# sismikenkazmod.net
KiCad netlist of a schematic drawn in Altium Designer
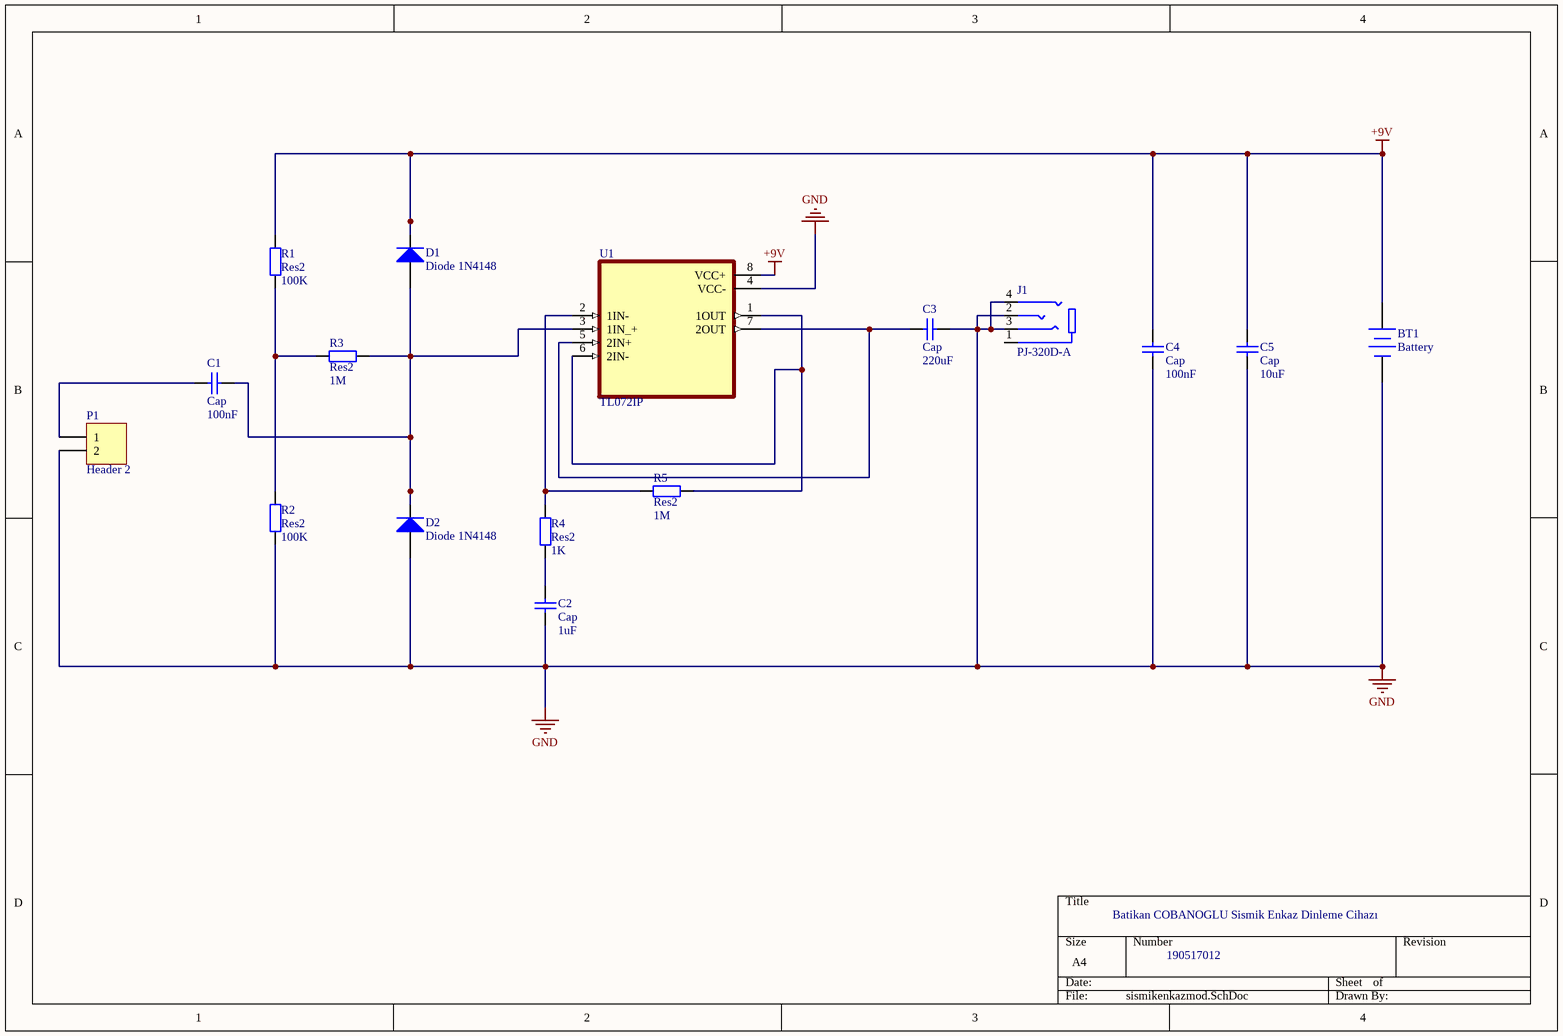
[diagram p0: sismikenkazmod.SchDoc]

(export (version "E")
  (design (tool "Eeschema 10.0.6"))
  (components
    (comp (ref "BT1")
      (value "Battery")
      (footprint "BAT-2")
      (description "Multicell Battery")
      (fields (field (name "PUBLISHER") "Altium Limited"))
      (libsource (lib "Miscellaneous Devices") (part "Battery"))
    )
    (comp (ref "C1")
      (value "Cap")
      (footprint "RAD-0.3")
      (description "Capacitor")
      (fields (field (name "ALTIUM_VALUE") "100nF") (field (name "PUBLISHER") "Altium Limited"))
      (libsource (lib "Miscellaneous Devices") (part "Cap"))
    )
    (comp (ref "C2")
      (value "Cap")
      (footprint "RAD-0.3")
      (description "Capacitor")
      (fields (field (name "ALTIUM_VALUE") "1uF") (field (name "PUBLISHER") "Altium Limited"))
      (libsource (lib "Miscellaneous Devices") (part "Cap"))
    )
    (comp (ref "C3")
      (value "Cap")
      (footprint "RAD-0.3")
      (description "Capacitor")
      (fields (field (name "ALTIUM_VALUE") "220uF") (field (name "PUBLISHER") "Altium Limited"))
      (libsource (lib "Miscellaneous Devices") (part "Cap"))
    )
    (comp (ref "C4")
      (value "Cap")
      (footprint "RAD-0.3")
      (description "Capacitor")
      (fields (field (name "ALTIUM_VALUE") "100nF") (field (name "PUBLISHER") "Altium Limited"))
      (libsource (lib "Miscellaneous Devices") (part "Cap"))
    )
    (comp (ref "C5")
      (value "Cap")
      (footprint "RAD-0.3")
      (description "Capacitor")
      (fields (field (name "ALTIUM_VALUE") "10uF") (field (name "PUBLISHER") "Altium Limited"))
      (libsource (lib "Miscellaneous Devices") (part "Cap"))
    )
    (comp (ref "D1")
      (value "Diode 1N4148")
      (footprint "DO-35")
      (description "High Conductance Fast Diode")
      (fields (field (name "PUBLISHER") "Altium Limited"))
      (libsource (lib "Miscellaneous Devices") (part "Diode 1N4148"))
    )
    (comp (ref "D2")
      (value "Diode 1N4148")
      (footprint "DO-35")
      (description "High Conductance Fast Diode")
      (fields (field (name "PUBLISHER") "Altium Limited"))
      (libsource (lib "Miscellaneous Devices") (part "Diode 1N4148"))
    )
    (comp (ref "J1")
      (value "PJ-320D-A")
      (footprint "HRO_PJ-320D-A")
      (description "Headphone jack 0.5A 30V DC 100 mÎ©")
      (fields (field (name "MF") "HRO Electronics Co., Ltd."))
      (libsource (lib "PJ-320D-A") (part "PJ-320D-A"))
    )
    (comp (ref "P1")
      (value "Header 2")
      (footprint "HDR1X2")
      (description "Header, 2-Pin")
      (fields (field (name "PUBLISHER") "Altium Limited"))
      (libsource (lib "Miscellaneous Connectors") (part "Header 2"))
    )
    (comp (ref "R1")
      (value "Res2")
      (footprint "AXIAL-0.4")
      (description "Resistor")
      (fields (field (name "ALTIUM_VALUE") "100K") (field (name "PUBLISHER") "Altium Limited"))
      (libsource (lib "") (part "Res2_1"))
    )
    (comp (ref "R2")
      (value "Res2")
      (footprint "AXIAL-0.4")
      (description "Resistor")
      (fields (field (name "ALTIUM_VALUE") "100K") (field (name "PUBLISHER") "Altium Limited"))
      (libsource (lib "") (part "Res2_1"))
    )
    (comp (ref "R3")
      (value "Res2")
      (footprint "AXIAL-0.4")
      (description "Resistor")
      (fields (field (name "ALTIUM_VALUE") "1M") (field (name "PUBLISHER") "Altium Limited"))
      (libsource (lib "Miscellaneous Devices") (part "Res2"))
    )
    (comp (ref "R4")
      (value "Res2")
      (footprint "AXIAL-0.4")
      (description "Resistor")
      (fields (field (name "ALTIUM_VALUE") "1K") (field (name "PUBLISHER") "Altium Limited"))
      (libsource (lib "") (part "Res2_1"))
    )
    (comp (ref "R5")
      (value "Res2")
      (footprint "AXIAL-0.4")
      (description "Resistor")
      (fields (field (name "ALTIUM_VALUE") "1M") (field (name "PUBLISHER") "Altium Limited"))
      (libsource (lib "Miscellaneous Devices") (part "Res2"))
    )
    (comp (ref "U1")
      (value "TL072IP")
      (footprint "DIP794W45P254L959H508Q8")
      (description "Dual, 30-V, 3-MHz, high slew rate (13-V/Âµs), In to V+, JFET-input op amp")
      (fields (field (name "MF") "Texas Instruments"))
      (libsource (lib "TL072IP") (part "TL072IP"))
    )
  )
  (nets
    (net (code "1") (name "+9V") (class "Default")
      (node (ref "BT1") (pin "1") (pinfunction "+_1") (pintype "passive"))
      (node (ref "C4") (pin "1") (pinfunction "1_1") (pintype "passive"))
      (node (ref "C5") (pin "1") (pinfunction "1_1") (pintype "passive"))
      (node (ref "D1") (pin "2") (pinfunction "K_2") (pintype "passive"))
      (node (ref "R1") (pin "1") (pinfunction "1_1") (pintype "passive"))
      (node (ref "U1") (pin "8") (pinfunction "VCC+_8") (pintype "power_in"))
    )
    (net (code "2") (name "GND") (class "Default")
      (node (ref "BT1") (pin "2") (pinfunction "-_2") (pintype "passive"))
      (node (ref "C2") (pin "1") (pinfunction "1_1") (pintype "passive"))
      (node (ref "C3") (pin "2") (pinfunction "2_2") (pintype "passive"))
      (node (ref "C4") (pin "2") (pinfunction "2_2") (pintype "passive"))
      (node (ref "C5") (pin "2") (pinfunction "2_2") (pintype "passive"))
      (node (ref "D2") (pin "1") (pinfunction "A_1") (pintype "passive"))
      (node (ref "J1") (pin "2") (pinfunction "TIP_2") (pintype "passive"))
      (node (ref "J1") (pin "3") (pinfunction "RING1_3") (pintype "passive"))
      (node (ref "J1") (pin "4") (pinfunction "RING2_4") (pintype "passive"))
      (node (ref "P1") (pin "2") (pinfunction "2_2") (pintype "passive"))
      (node (ref "R2") (pin "2") (pinfunction "2_2") (pintype "passive"))
      (node (ref "U1") (pin "4") (pinfunction "VCC-_4") (pintype "power_in"))
    )
    (net (code "3") (name "Net-(C1-Pad1)") (class "Default")
      (node (ref "C1") (pin "1") (pinfunction "1_1") (pintype "passive"))
      (node (ref "P1") (pin "1") (pinfunction "1_1") (pintype "passive"))
    )
    (net (code "4") (name "Net-(C2-Pad2)") (class "Default")
      (node (ref "C2") (pin "2") (pinfunction "2_2") (pintype "passive"))
      (node (ref "R4") (pin "2") (pinfunction "2_2") (pintype "passive"))
    )
    (net (code "5") (name "Net-(D1-A)") (class "Default")
      (node (ref "C1") (pin "2") (pinfunction "2_2") (pintype "passive"))
      (node (ref "D1") (pin "1") (pinfunction "A_1") (pintype "passive"))
      (node (ref "D2") (pin "2") (pinfunction "K_2") (pintype "passive"))
      (node (ref "R3") (pin "2") (pinfunction "2_2") (pintype "passive"))
      (node (ref "U1") (pin "3") (pinfunction "1IN_+_3") (pintype "input"))
    )
    (net (code "6") (name "Net-(R1-Pad2)") (class "Default")
      (node (ref "R1") (pin "2") (pinfunction "2_2") (pintype "passive"))
      (node (ref "R2") (pin "1") (pinfunction "1_1") (pintype "passive"))
      (node (ref "R3") (pin "1") (pinfunction "1_1") (pintype "passive"))
    )
    (net (code "7") (name "Net-(U1-1IN-)") (class "Default")
      (node (ref "R4") (pin "1") (pinfunction "1_1") (pintype "passive"))
      (node (ref "R5") (pin "1") (pinfunction "1_1") (pintype "passive"))
      (node (ref "U1") (pin "2") (pinfunction "1IN-_2") (pintype "input"))
    )
    (net (code "8") (name "Net-(U1-1OUT)") (class "Default")
      (node (ref "R5") (pin "2") (pinfunction "2_2") (pintype "passive"))
      (node (ref "U1") (pin "1") (pinfunction "1OUT_1") (pintype "output"))
      (node (ref "U1") (pin "6") (pinfunction "2IN-_6") (pintype "input"))
    )
    (net (code "9") (name "Net-(U1-2IN+)") (class "Default")
      (node (ref "C3") (pin "1") (pinfunction "1_1") (pintype "passive"))
      (node (ref "U1") (pin "5") (pinfunction "2IN+_5") (pintype "input"))
      (node (ref "U1") (pin "7") (pinfunction "2OUT_7") (pintype "output"))
    )
    (net (code "10") (name "unconnected-(J1-SLEEVE-Pad1)") (class "Default")
      (node (ref "J1") (pin "1") (pinfunction "SLEEVE_1") (pintype "passive"))
    )
  )
)
